# pcb9_21.net
KiCad netlist of a schematic drawn in EAGLE
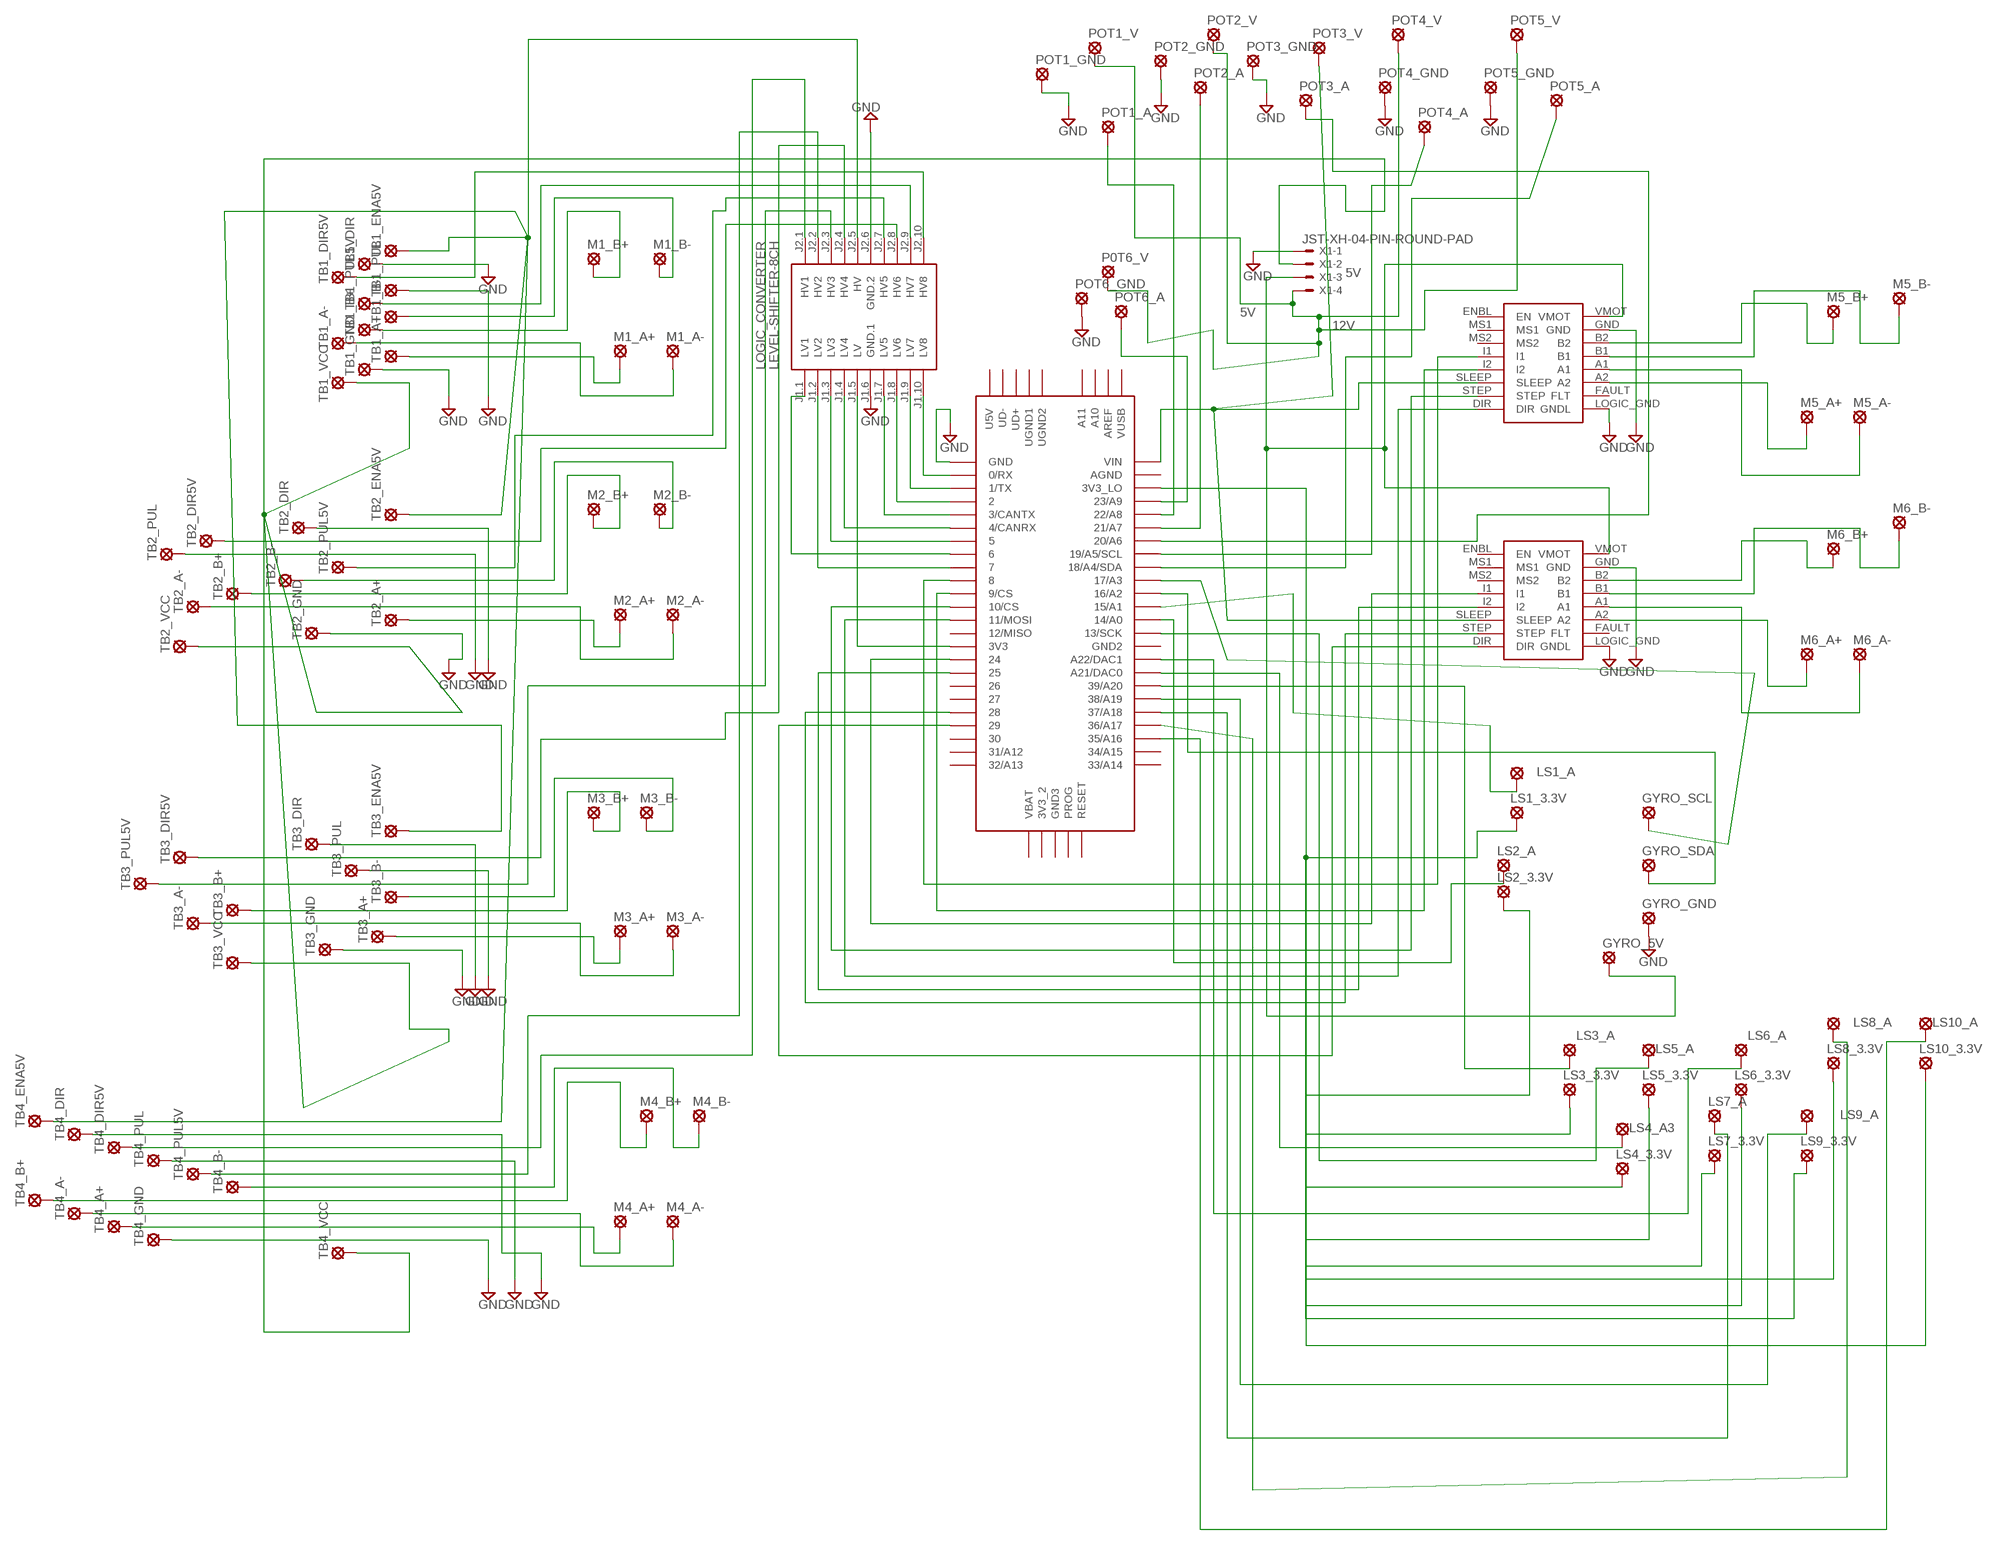
[diagram p0: schematic, sheet 1]

(export (version "E")
  (design (tool "Eeschema 10.0.6"))
  (components
    (comp (ref "GYRO_5V")
      (value "LSP11")
      (footprint "eagle-import:LSP11")
      (libsource (lib "eagle-import") (part "LSP11"))
    )
    (comp (ref "GYRO_GND")
      (value "LSP11")
      (footprint "eagle-import:LSP11")
      (libsource (lib "eagle-import") (part "LSP11"))
    )
    (comp (ref "GYRO_SCL")
      (value "LSP11")
      (footprint "eagle-import:LSP11")
      (libsource (lib "eagle-import") (part "LSP11"))
    )
    (comp (ref "GYRO_SDA")
      (value "LSP11")
      (footprint "eagle-import:LSP11")
      (libsource (lib "eagle-import") (part "LSP11"))
    )
    (comp (ref "LOGIC_CONVERTER")
      (value "LEVEL-SHIFTER-8CH")
      (footprint "eagle-import:LEVEL-SHIFTER-8CH")
      (libsource (lib "eagle-import") (part "LEVEL-SHIFTER-8CH"))
    )
    (comp (ref "LS1_3.3V")
      (value "LSP11")
      (footprint "eagle-import:LSP11")
      (libsource (lib "eagle-import") (part "LSP11"))
    )
    (comp (ref "LS1_A")
      (value "LSP11")
      (footprint "eagle-import:LSP11")
      (libsource (lib "eagle-import") (part "LSP11"))
    )
    (comp (ref "LS2_3.3V")
      (value "LSP11")
      (footprint "eagle-import:LSP11")
      (libsource (lib "eagle-import") (part "LSP11"))
    )
    (comp (ref "LS2_A")
      (value "LSP11")
      (footprint "eagle-import:LSP11")
      (libsource (lib "eagle-import") (part "LSP11"))
    )
    (comp (ref "LS3_3.3V")
      (value "LSP11")
      (footprint "eagle-import:LSP11")
      (libsource (lib "eagle-import") (part "LSP11"))
    )
    (comp (ref "LS3_A")
      (value "LSP11")
      (footprint "eagle-import:LSP11")
      (libsource (lib "eagle-import") (part "LSP11"))
    )
    (comp (ref "LS4_3.3V")
      (value "LSP11")
      (footprint "eagle-import:LSP11")
      (libsource (lib "eagle-import") (part "LSP11"))
    )
    (comp (ref "LS4_A3")
      (value "LSP11")
      (footprint "eagle-import:LSP11")
      (libsource (lib "eagle-import") (part "LSP11"))
    )
    (comp (ref "LS5_3.3V")
      (value "LSP11")
      (footprint "eagle-import:LSP11")
      (libsource (lib "eagle-import") (part "LSP11"))
    )
    (comp (ref "LS5_A")
      (value "LSP11")
      (footprint "eagle-import:LSP11")
      (libsource (lib "eagle-import") (part "LSP11"))
    )
    (comp (ref "LS6_3.3V")
      (value "LSP11")
      (footprint "eagle-import:LSP11")
      (libsource (lib "eagle-import") (part "LSP11"))
    )
    (comp (ref "LS6_A")
      (value "LSP11")
      (footprint "eagle-import:LSP11")
      (libsource (lib "eagle-import") (part "LSP11"))
    )
    (comp (ref "LS7_3.3V")
      (value "LSP11")
      (footprint "eagle-import:LSP11")
      (libsource (lib "eagle-import") (part "LSP11"))
    )
    (comp (ref "LS7_A")
      (value "LSP11")
      (footprint "eagle-import:LSP11")
      (libsource (lib "eagle-import") (part "LSP11"))
    )
    (comp (ref "LS8_3.3V")
      (value "LSP11")
      (footprint "eagle-import:LSP11")
      (libsource (lib "eagle-import") (part "LSP11"))
    )
    (comp (ref "LS8_A")
      (value "LSP11")
      (footprint "eagle-import:LSP11")
      (libsource (lib "eagle-import") (part "LSP11"))
    )
    (comp (ref "LS9_3.3V")
      (value "LSP11")
      (footprint "eagle-import:LSP11")
      (libsource (lib "eagle-import") (part "LSP11"))
    )
    (comp (ref "LS9_A")
      (value "LSP11")
      (footprint "eagle-import:LSP11")
      (libsource (lib "eagle-import") (part "LSP11"))
    )
    (comp (ref "LS10_3.3V")
      (value "LSP11")
      (footprint "eagle-import:LSP11")
      (libsource (lib "eagle-import") (part "LSP11"))
    )
    (comp (ref "LS10_A")
      (value "LSP11")
      (footprint "eagle-import:LSP11")
      (libsource (lib "eagle-import") (part "LSP11"))
    )
    (comp (ref "M1_A+")
      (value "LSP11")
      (footprint "eagle-import:LSP11")
      (libsource (lib "eagle-import") (part "LSP11"))
    )
    (comp (ref "M1_A-")
      (value "LSP11")
      (footprint "eagle-import:LSP11")
      (libsource (lib "eagle-import") (part "LSP11"))
    )
    (comp (ref "M1_B+")
      (value "LSP11")
      (footprint "eagle-import:LSP11")
      (libsource (lib "eagle-import") (part "LSP11"))
    )
    (comp (ref "M1_B-")
      (value "LSP11")
      (footprint "eagle-import:LSP11")
      (libsource (lib "eagle-import") (part "LSP11"))
    )
    (comp (ref "M2_A+")
      (value "LSP11")
      (footprint "eagle-import:LSP11")
      (libsource (lib "eagle-import") (part "LSP11"))
    )
    (comp (ref "M2_A-")
      (value "LSP11")
      (footprint "eagle-import:LSP11")
      (libsource (lib "eagle-import") (part "LSP11"))
    )
    (comp (ref "M2_B+")
      (value "LSP11")
      (footprint "eagle-import:LSP11")
      (libsource (lib "eagle-import") (part "LSP11"))
    )
    (comp (ref "M2_B-")
      (value "LSP11")
      (footprint "eagle-import:LSP11")
      (libsource (lib "eagle-import") (part "LSP11"))
    )
    (comp (ref "M3_A+")
      (value "LSP11")
      (footprint "eagle-import:LSP11")
      (libsource (lib "eagle-import") (part "LSP11"))
    )
    (comp (ref "M3_A-")
      (value "LSP11")
      (footprint "eagle-import:LSP11")
      (libsource (lib "eagle-import") (part "LSP11"))
    )
    (comp (ref "M3_B+")
      (value "LSP11")
      (footprint "eagle-import:LSP11")
      (libsource (lib "eagle-import") (part "LSP11"))
    )
    (comp (ref "M3_B-")
      (value "LSP11")
      (footprint "eagle-import:LSP11")
      (libsource (lib "eagle-import") (part "LSP11"))
    )
    (comp (ref "M4_A+")
      (value "LSP11")
      (footprint "eagle-import:LSP11")
      (libsource (lib "eagle-import") (part "LSP11"))
    )
    (comp (ref "M4_A-")
      (value "LSP11")
      (footprint "eagle-import:LSP11")
      (libsource (lib "eagle-import") (part "LSP11"))
    )
    (comp (ref "M4_B+")
      (value "LSP11")
      (footprint "eagle-import:LSP11")
      (libsource (lib "eagle-import") (part "LSP11"))
    )
    (comp (ref "M4_B-")
      (value "LSP11")
      (footprint "eagle-import:LSP11")
      (libsource (lib "eagle-import") (part "LSP11"))
    )
    (comp (ref "M5_A+")
      (value "LSP11")
      (footprint "eagle-import:LSP11")
      (libsource (lib "eagle-import") (part "LSP11"))
    )
    (comp (ref "M5_A-")
      (value "LSP11")
      (footprint "eagle-import:LSP11")
      (libsource (lib "eagle-import") (part "LSP11"))
    )
    (comp (ref "M5_B+")
      (value "LSP11")
      (footprint "eagle-import:LSP11")
      (libsource (lib "eagle-import") (part "LSP11"))
    )
    (comp (ref "M5_B-")
      (value "LSP11")
      (footprint "eagle-import:LSP11")
      (libsource (lib "eagle-import") (part "LSP11"))
    )
    (comp (ref "M6_A+")
      (value "LSP11")
      (footprint "eagle-import:LSP11")
      (libsource (lib "eagle-import") (part "LSP11"))
    )
    (comp (ref "M6_A-")
      (value "LSP11")
      (footprint "eagle-import:LSP11")
      (libsource (lib "eagle-import") (part "LSP11"))
    )
    (comp (ref "M6_B+")
      (value "LSP11")
      (footprint "eagle-import:LSP11")
      (libsource (lib "eagle-import") (part "LSP11"))
    )
    (comp (ref "M6_B-")
      (value "LSP11")
      (footprint "eagle-import:LSP11")
      (libsource (lib "eagle-import") (part "LSP11"))
    )
    (comp (ref "MP6500_1")
      (value "MP6500THROUGH_HOLE")
      (footprint "eagle-import:MP6500")
      (libsource (lib "eagle-import") (part "MP6500THROUGH_HOLE"))
    )
    (comp (ref "MP6500_2")
      (value "MP6500THROUGH_HOLE")
      (footprint "eagle-import:MP6500")
      (libsource (lib "eagle-import") (part "MP6500THROUGH_HOLE"))
    )
    (comp (ref "P0T6_V")
      (value "LSP11")
      (footprint "eagle-import:LSP11")
      (libsource (lib "eagle-import") (part "LSP11"))
    )
    (comp (ref "POT1_A")
      (value "LSP11")
      (footprint "eagle-import:LSP11")
      (libsource (lib "eagle-import") (part "LSP11"))
    )
    (comp (ref "POT1_GND")
      (value "LSP11")
      (footprint "eagle-import:LSP11")
      (libsource (lib "eagle-import") (part "LSP11"))
    )
    (comp (ref "POT1_V")
      (value "LSP11")
      (footprint "eagle-import:LSP11")
      (libsource (lib "eagle-import") (part "LSP11"))
    )
    (comp (ref "POT2_A")
      (value "LSP11")
      (footprint "eagle-import:LSP11")
      (libsource (lib "eagle-import") (part "LSP11"))
    )
    (comp (ref "POT2_GND")
      (value "LSP11")
      (footprint "eagle-import:LSP11")
      (libsource (lib "eagle-import") (part "LSP11"))
    )
    (comp (ref "POT2_V")
      (value "LSP11")
      (footprint "eagle-import:LSP11")
      (libsource (lib "eagle-import") (part "LSP11"))
    )
    (comp (ref "POT3_A")
      (value "LSP11")
      (footprint "eagle-import:LSP11")
      (libsource (lib "eagle-import") (part "LSP11"))
    )
    (comp (ref "POT3_GND")
      (value "LSP11")
      (footprint "eagle-import:LSP11")
      (libsource (lib "eagle-import") (part "LSP11"))
    )
    (comp (ref "POT3_V")
      (value "LSP11")
      (footprint "eagle-import:LSP11")
      (libsource (lib "eagle-import") (part "LSP11"))
    )
    (comp (ref "POT4_A")
      (value "LSP11")
      (footprint "eagle-import:LSP11")
      (libsource (lib "eagle-import") (part "LSP11"))
    )
    (comp (ref "POT4_GND")
      (value "LSP11")
      (footprint "eagle-import:LSP11")
      (libsource (lib "eagle-import") (part "LSP11"))
    )
    (comp (ref "POT4_V")
      (value "LSP11")
      (footprint "eagle-import:LSP11")
      (libsource (lib "eagle-import") (part "LSP11"))
    )
    (comp (ref "POT5_A")
      (value "LSP11")
      (footprint "eagle-import:LSP11")
      (libsource (lib "eagle-import") (part "LSP11"))
    )
    (comp (ref "POT5_GND")
      (value "LSP11")
      (footprint "eagle-import:LSP11")
      (libsource (lib "eagle-import") (part "LSP11"))
    )
    (comp (ref "POT5_V")
      (value "LSP11")
      (footprint "eagle-import:LSP11")
      (libsource (lib "eagle-import") (part "LSP11"))
    )
    (comp (ref "POT6_A")
      (value "LSP11")
      (footprint "eagle-import:LSP11")
      (libsource (lib "eagle-import") (part "LSP11"))
    )
    (comp (ref "POT6_GND")
      (value "LSP11")
      (footprint "eagle-import:LSP11")
      (libsource (lib "eagle-import") (part "LSP11"))
    )
    (comp (ref "TB1_A+")
      (value "LSP11")
      (footprint "eagle-import:LSP11")
      (libsource (lib "eagle-import") (part "LSP11"))
    )
    (comp (ref "TB1_A-")
      (value "LSP11")
      (footprint "eagle-import:LSP11")
      (libsource (lib "eagle-import") (part "LSP11"))
    )
    (comp (ref "TB1_B+")
      (value "LSP11")
      (footprint "eagle-import:LSP11")
      (libsource (lib "eagle-import") (part "LSP11"))
    )
    (comp (ref "TB1_B-")
      (value "LSP11")
      (footprint "eagle-import:LSP11")
      (libsource (lib "eagle-import") (part "LSP11"))
    )
    (comp (ref "TB1_DIR")
      (value "LSP11")
      (footprint "eagle-import:LSP11")
      (libsource (lib "eagle-import") (part "LSP11"))
    )
    (comp (ref "TB1_DIR5V")
      (value "LSP11")
      (footprint "eagle-import:LSP11")
      (libsource (lib "eagle-import") (part "LSP11"))
    )
    (comp (ref "TB1_ENA5V")
      (value "LSP11")
      (footprint "eagle-import:LSP11")
      (libsource (lib "eagle-import") (part "LSP11"))
    )
    (comp (ref "TB1_GND")
      (value "LSP11")
      (footprint "eagle-import:LSP11")
      (libsource (lib "eagle-import") (part "LSP11"))
    )
    (comp (ref "TB1_PUL")
      (value "LSP11")
      (footprint "eagle-import:LSP11")
      (libsource (lib "eagle-import") (part "LSP11"))
    )
    (comp (ref "TB1_PUL5V")
      (value "LSP11")
      (footprint "eagle-import:LSP11")
      (libsource (lib "eagle-import") (part "LSP11"))
    )
    (comp (ref "TB1_VCC")
      (value "LSP11")
      (footprint "eagle-import:LSP11")
      (libsource (lib "eagle-import") (part "LSP11"))
    )
    (comp (ref "TB2_A+")
      (value "LSP11")
      (footprint "eagle-import:LSP11")
      (libsource (lib "eagle-import") (part "LSP11"))
    )
    (comp (ref "TB2_A-")
      (value "LSP11")
      (footprint "eagle-import:LSP11")
      (libsource (lib "eagle-import") (part "LSP11"))
    )
    (comp (ref "TB2_B+")
      (value "LSP11")
      (footprint "eagle-import:LSP11")
      (libsource (lib "eagle-import") (part "LSP11"))
    )
    (comp (ref "TB2_B-")
      (value "LSP11")
      (footprint "eagle-import:LSP11")
      (libsource (lib "eagle-import") (part "LSP11"))
    )
    (comp (ref "TB2_DIR")
      (value "LSP11")
      (footprint "eagle-import:LSP11")
      (libsource (lib "eagle-import") (part "LSP11"))
    )
    (comp (ref "TB2_DIR5V")
      (value "LSP11")
      (footprint "eagle-import:LSP11")
      (libsource (lib "eagle-import") (part "LSP11"))
    )
    (comp (ref "TB2_ENA5V")
      (value "LSP11")
      (footprint "eagle-import:LSP11")
      (libsource (lib "eagle-import") (part "LSP11"))
    )
    (comp (ref "TB2_GND")
      (value "LSP11")
      (footprint "eagle-import:LSP11")
      (libsource (lib "eagle-import") (part "LSP11"))
    )
    (comp (ref "TB2_PUL")
      (value "LSP11")
      (footprint "eagle-import:LSP11")
      (libsource (lib "eagle-import") (part "LSP11"))
    )
    (comp (ref "TB2_PUL5V")
      (value "LSP11")
      (footprint "eagle-import:LSP11")
      (libsource (lib "eagle-import") (part "LSP11"))
    )
    (comp (ref "TB2_VCC")
      (value "LSP11")
      (footprint "eagle-import:LSP11")
      (libsource (lib "eagle-import") (part "LSP11"))
    )
    (comp (ref "TB3_A+")
      (value "LSP11")
      (footprint "eagle-import:LSP11")
      (libsource (lib "eagle-import") (part "LSP11"))
    )
    (comp (ref "TB3_A-")
      (value "LSP11")
      (footprint "eagle-import:LSP11")
      (libsource (lib "eagle-import") (part "LSP11"))
    )
    (comp (ref "TB3_B+")
      (value "LSP11")
      (footprint "eagle-import:LSP11")
      (libsource (lib "eagle-import") (part "LSP11"))
    )
    (comp (ref "TB3_B-")
      (value "LSP11")
      (footprint "eagle-import:LSP11")
      (libsource (lib "eagle-import") (part "LSP11"))
    )
    (comp (ref "TB3_DIR")
      (value "LSP11")
      (footprint "eagle-import:LSP11")
      (libsource (lib "eagle-import") (part "LSP11"))
    )
    (comp (ref "TB3_DIR5V")
      (value "LSP11")
      (footprint "eagle-import:LSP11")
      (libsource (lib "eagle-import") (part "LSP11"))
    )
    (comp (ref "TB3_ENA5V")
      (value "LSP11")
      (footprint "eagle-import:LSP11")
      (libsource (lib "eagle-import") (part "LSP11"))
    )
    (comp (ref "TB3_GND")
      (value "LSP11")
      (footprint "eagle-import:LSP11")
      (libsource (lib "eagle-import") (part "LSP11"))
    )
    (comp (ref "TB3_PUL")
      (value "LSP11")
      (footprint "eagle-import:LSP11")
      (libsource (lib "eagle-import") (part "LSP11"))
    )
    (comp (ref "TB3_PUL5V")
      (value "LSP11")
      (footprint "eagle-import:LSP11")
      (libsource (lib "eagle-import") (part "LSP11"))
    )
    (comp (ref "TB3_VCC")
      (value "LSP11")
      (footprint "eagle-import:LSP11")
      (libsource (lib "eagle-import") (part "LSP11"))
    )
    (comp (ref "TB4_A+")
      (value "LSP11")
      (footprint "eagle-import:LSP11")
      (libsource (lib "eagle-import") (part "LSP11"))
    )
    (comp (ref "TB4_A-")
      (value "LSP11")
      (footprint "eagle-import:LSP11")
      (libsource (lib "eagle-import") (part "LSP11"))
    )
    (comp (ref "TB4_B+")
      (value "LSP11")
      (footprint "eagle-import:LSP11")
      (libsource (lib "eagle-import") (part "LSP11"))
    )
    (comp (ref "TB4_B-")
      (value "LSP11")
      (footprint "eagle-import:LSP11")
      (libsource (lib "eagle-import") (part "LSP11"))
    )
    (comp (ref "TB4_DIR")
      (value "LSP11")
      (footprint "eagle-import:LSP11")
      (libsource (lib "eagle-import") (part "LSP11"))
    )
    (comp (ref "TB4_DIR5V")
      (value "LSP11")
      (footprint "eagle-import:LSP11")
      (libsource (lib "eagle-import") (part "LSP11"))
    )
    (comp (ref "TB4_ENA5V")
      (value "LSP11")
      (footprint "eagle-import:LSP11")
      (libsource (lib "eagle-import") (part "LSP11"))
    )
    (comp (ref "TB4_GND")
      (value "LSP11")
      (footprint "eagle-import:LSP11")
      (libsource (lib "eagle-import") (part "LSP11"))
    )
    (comp (ref "TB4_PUL")
      (value "LSP11")
      (footprint "eagle-import:LSP11")
      (libsource (lib "eagle-import") (part "LSP11"))
    )
    (comp (ref "TB4_PUL5V")
      (value "LSP11")
      (footprint "eagle-import:LSP11")
      (libsource (lib "eagle-import") (part "LSP11"))
    )
    (comp (ref "TB4_VCC")
      (value "LSP11")
      (footprint "eagle-import:LSP11")
      (libsource (lib "eagle-import") (part "LSP11"))
    )
    (comp (ref "TEENSY4.1")
      (value "TEENSY_3.5/3.6")
      (footprint "eagle-import:TEENSY_3.5_3.6")
      (libsource (lib "eagle-import") (part "TEENSY_3.5/3.6"))
    )
    (comp (ref "X1")
      (value "JST-XH-04-PIN-ROUND-PAD")
      (footprint "eagle-import:JST-XH-04-PACKAGE-ROUND-PAD")
      (libsource (lib "eagle-import") (part "JST-XH-04-PIN-ROUND-PAD"))
    )
  )
  (nets
    (net (code "1") (name "/5V") (class "Default")
      (node (ref "GYRO_5V") (pin "MP") (pinfunction "MP_MP") (pintype "passive"))
      (node (ref "MP6500_1") (pin "VMOT") (pinfunction "VMOT_VMOT") (pintype "bidirectional"))
      (node (ref "MP6500_2") (pin "VMOT") (pinfunction "VMOT_VMOT") (pintype "bidirectional"))
      (node (ref "TB1_VCC") (pin "MP") (pinfunction "MP_MP") (pintype "passive"))
      (node (ref "TB2_VCC") (pin "MP") (pinfunction "MP_MP") (pintype "passive"))
      (node (ref "TB3_VCC") (pin "MP") (pinfunction "MP_MP") (pintype "passive"))
      (node (ref "TB4_VCC") (pin "MP") (pinfunction "MP_MP") (pintype "passive"))
      (node (ref "X1") (pin "2") (pinfunction "S_2") (pintype "passive"))
      (node (ref "X1") (pin "3") (pinfunction "S_3") (pintype "passive"))
    )
    (net (code "2") (name "/12V") (class "Default")
      (node (ref "P0T6_V") (pin "MP") (pinfunction "MP_MP") (pintype "passive"))
      (node (ref "POT1_V") (pin "MP") (pinfunction "MP_MP") (pintype "passive"))
      (node (ref "POT2_V") (pin "MP") (pinfunction "MP_MP") (pintype "passive"))
      (node (ref "POT4_V") (pin "MP") (pinfunction "MP_MP") (pintype "passive"))
      (node (ref "POT5_V") (pin "MP") (pinfunction "MP_MP") (pintype "passive"))
      (node (ref "X1") (pin "4") (pinfunction "S_4") (pintype "passive"))
    )
    (net (code "3") (name "GND") (class "Default")
      (node (ref "GYRO_GND") (pin "MP") (pinfunction "MP_MP") (pintype "passive"))
      (node (ref "LOGIC_CONVERTER") (pin "J1.6") (pinfunction "GND.1_J1.6") (pintype "power_in"))
      (node (ref "LOGIC_CONVERTER") (pin "J2.6") (pinfunction "GND.2_J2.6") (pintype "power_in"))
      (node (ref "MP6500_1") (pin "GND") (pinfunction "GND_GND") (pintype "bidirectional"))
      (node (ref "MP6500_1") (pin "LOGIC_GND") (pinfunction "GNDL_LOGIC_GND") (pintype "bidirectional"))
      (node (ref "MP6500_2") (pin "GND") (pinfunction "GND_GND") (pintype "bidirectional"))
      (node (ref "MP6500_2") (pin "LOGIC_GND") (pinfunction "GNDL_LOGIC_GND") (pintype "bidirectional"))
      (node (ref "POT1_GND") (pin "MP") (pinfunction "MP_MP") (pintype "passive"))
      (node (ref "POT2_GND") (pin "MP") (pinfunction "MP_MP") (pintype "passive"))
      (node (ref "POT3_GND") (pin "MP") (pinfunction "MP_MP") (pintype "passive"))
      (node (ref "POT4_GND") (pin "MP") (pinfunction "MP_MP") (pintype "passive"))
      (node (ref "POT5_GND") (pin "MP") (pinfunction "MP_MP") (pintype "passive"))
      (node (ref "POT6_GND") (pin "MP") (pinfunction "MP_MP") (pintype "passive"))
      (node (ref "TB1_DIR") (pin "MP") (pinfunction "MP_MP") (pintype "passive"))
      (node (ref "TB1_GND") (pin "MP") (pinfunction "MP_MP") (pintype "passive"))
      (node (ref "TB1_PUL") (pin "MP") (pinfunction "MP_MP") (pintype "passive"))
      (node (ref "TB2_DIR") (pin "MP") (pinfunction "MP_MP") (pintype "passive"))
      (node (ref "TB2_GND") (pin "MP") (pinfunction "MP_MP") (pintype "passive"))
      (node (ref "TB2_PUL") (pin "MP") (pinfunction "MP_MP") (pintype "passive"))
      (node (ref "TB3_DIR") (pin "MP") (pinfunction "MP_MP") (pintype "passive"))
      (node (ref "TB3_GND") (pin "MP") (pinfunction "MP_MP") (pintype "passive"))
      (node (ref "TB3_PUL") (pin "MP") (pinfunction "MP_MP") (pintype "passive"))
      (node (ref "TB4_DIR") (pin "MP") (pinfunction "MP_MP") (pintype "passive"))
      (node (ref "TB4_GND") (pin "MP") (pinfunction "MP_MP") (pintype "passive"))
      (node (ref "TB4_PUL") (pin "MP") (pinfunction "MP_MP") (pintype "passive"))
      (node (ref "TEENSY4.1") (pin "GND") (pinfunction "GND_GND") (pintype "bidirectional"))
      (node (ref "X1") (pin "1") (pinfunction "S_1") (pintype "passive"))
    )
    (net (code "4") (name "Net-(GYRO_SCL-PadMP)") (class "Default")
      (node (ref "GYRO_SCL") (pin "MP") (pinfunction "MP_MP") (pintype "passive"))
      (node (ref "TEENSY4.1") (pin "17/A3") (pinfunction "17/A3_17/A3") (pintype "bidirectional"))
    )
    (net (code "5") (name "Net-(GYRO_SDA-PadMP)") (class "Default")
      (node (ref "GYRO_SDA") (pin "MP") (pinfunction "MP_MP") (pintype "passive"))
      (node (ref "TEENSY4.1") (pin "16/A2") (pinfunction "16/A2_16/A2") (pintype "bidirectional"))
    )
    (net (code "6") (name "Net-(LOGIC_CONVERTER-HV)") (class "Default")
      (node (ref "LOGIC_CONVERTER") (pin "J2.5") (pinfunction "HV_J2.5") (pintype "power_in"))
      (node (ref "TB1_ENA5V") (pin "MP") (pinfunction "MP_MP") (pintype "passive"))
      (node (ref "TB2_ENA5V") (pin "MP") (pinfunction "MP_MP") (pintype "passive"))
      (node (ref "TB3_ENA5V") (pin "MP") (pinfunction "MP_MP") (pintype "passive"))
      (node (ref "TB4_ENA5V") (pin "MP") (pinfunction "MP_MP") (pintype "passive"))
    )
    (net (code "7") (name "Net-(LOGIC_CONVERTER-HV1)") (class "Default")
      (node (ref "LOGIC_CONVERTER") (pin "J2.1") (pinfunction "HV1_J2.1") (pintype "bidirectional"))
      (node (ref "TB4_DIR5V") (pin "MP") (pinfunction "MP_MP") (pintype "passive"))
    )
    (net (code "8") (name "Net-(LOGIC_CONVERTER-HV2)") (class "Default")
      (node (ref "LOGIC_CONVERTER") (pin "J2.2") (pinfunction "HV2_J2.2") (pintype "bidirectional"))
      (node (ref "TB4_PUL5V") (pin "MP") (pinfunction "MP_MP") (pintype "passive"))
    )
    (net (code "9") (name "Net-(LOGIC_CONVERTER-HV3)") (class "Default")
      (node (ref "LOGIC_CONVERTER") (pin "J2.3") (pinfunction "HV3_J2.3") (pintype "bidirectional"))
      (node (ref "TB3_PUL5V") (pin "MP") (pinfunction "MP_MP") (pintype "passive"))
    )
    (net (code "10") (name "Net-(LOGIC_CONVERTER-HV4)") (class "Default")
      (node (ref "LOGIC_CONVERTER") (pin "J2.4") (pinfunction "HV4_J2.4") (pintype "bidirectional"))
      (node (ref "TB3_DIR5V") (pin "MP") (pinfunction "MP_MP") (pintype "passive"))
    )
    (net (code "11") (name "Net-(LOGIC_CONVERTER-HV5)") (class "Default")
      (node (ref "LOGIC_CONVERTER") (pin "J2.7") (pinfunction "HV5_J2.7") (pintype "bidirectional"))
      (node (ref "TB2_PUL5V") (pin "MP") (pinfunction "MP_MP") (pintype "passive"))
    )
    (net (code "12") (name "Net-(LOGIC_CONVERTER-HV6)") (class "Default")
      (node (ref "LOGIC_CONVERTER") (pin "J2.8") (pinfunction "HV6_J2.8") (pintype "bidirectional"))
      (node (ref "TB2_DIR5V") (pin "MP") (pinfunction "MP_MP") (pintype "passive"))
    )
    (net (code "13") (name "Net-(LOGIC_CONVERTER-HV7)") (class "Default")
      (node (ref "LOGIC_CONVERTER") (pin "J2.9") (pinfunction "HV7_J2.9") (pintype "bidirectional"))
      (node (ref "TB1_PUL5V") (pin "MP") (pinfunction "MP_MP") (pintype "passive"))
    )
    (net (code "14") (name "Net-(LOGIC_CONVERTER-HV8)") (class "Default")
      (node (ref "LOGIC_CONVERTER") (pin "J2.10") (pinfunction "HV8_J2.10") (pintype "bidirectional"))
      (node (ref "TB1_DIR5V") (pin "MP") (pinfunction "MP_MP") (pintype "passive"))
    )
    (net (code "15") (name "Net-(LOGIC_CONVERTER-LV)") (class "Default")
      (node (ref "LOGIC_CONVERTER") (pin "J1.5") (pinfunction "LV_J1.5") (pintype "power_in"))
      (node (ref "TEENSY4.1") (pin "3V3") (pinfunction "3V3_3V3") (pintype "bidirectional"))
    )
    (net (code "16") (name "Net-(LOGIC_CONVERTER-LV1)") (class "Default")
      (node (ref "LOGIC_CONVERTER") (pin "J1.1") (pinfunction "LV1_J1.1") (pintype "bidirectional"))
      (node (ref "TEENSY4.1") (pin "6") (pinfunction "6_6") (pintype "bidirectional"))
    )
    (net (code "17") (name "Net-(LOGIC_CONVERTER-LV2)") (class "Default")
      (node (ref "LOGIC_CONVERTER") (pin "J1.2") (pinfunction "LV2_J1.2") (pintype "bidirectional"))
      (node (ref "TEENSY4.1") (pin "7") (pinfunction "7_7") (pintype "bidirectional"))
    )
    (net (code "18") (name "Net-(LOGIC_CONVERTER-LV3)") (class "Default")
      (node (ref "LOGIC_CONVERTER") (pin "J1.3") (pinfunction "LV3_J1.3") (pintype "bidirectional"))
      (node (ref "TEENSY4.1") (pin "5") (pinfunction "5_5") (pintype "bidirectional"))
    )
    (net (code "19") (name "Net-(LOGIC_CONVERTER-LV4)") (class "Default")
      (node (ref "LOGIC_CONVERTER") (pin "J1.4") (pinfunction "LV4_J1.4") (pintype "bidirectional"))
      (node (ref "TEENSY4.1") (pin "4/CANRX") (pinfunction "4/CANRX_4/CANRX") (pintype "bidirectional"))
    )
    (net (code "20") (name "Net-(LOGIC_CONVERTER-LV5)") (class "Default")
      (node (ref "LOGIC_CONVERTER") (pin "J1.7") (pinfunction "LV5_J1.7") (pintype "bidirectional"))
      (node (ref "TEENSY4.1") (pin "3/CANTX") (pinfunction "3/CANTX_3/CANTX") (pintype "bidirectional"))
    )
    (net (code "21") (name "Net-(LOGIC_CONVERTER-LV6)") (class "Default")
      (node (ref "LOGIC_CONVERTER") (pin "J1.8") (pinfunction "LV6_J1.8") (pintype "bidirectional"))
      (node (ref "TEENSY4.1") (pin "2") (pinfunction "2_2") (pintype "bidirectional"))
    )
    (net (code "22") (name "Net-(LOGIC_CONVERTER-LV7)") (class "Default")
      (node (ref "LOGIC_CONVERTER") (pin "J1.9") (pinfunction "LV7_J1.9") (pintype "bidirectional"))
      (node (ref "TEENSY4.1") (pin "1/TX") (pinfunction "1/TX_1/TX") (pintype "bidirectional"))
    )
    (net (code "23") (name "Net-(LOGIC_CONVERTER-LV8)") (class "Default")
      (node (ref "LOGIC_CONVERTER") (pin "J1.10") (pinfunction "LV8_J1.10") (pintype "bidirectional"))
      (node (ref "TEENSY4.1") (pin "0/RX") (pinfunction "0/RX_0/RX") (pintype "bidirectional"))
    )
    (net (code "24") (name "Net-(LS1_A-PadMP)") (class "Default")
      (node (ref "LS1_A") (pin "MP") (pinfunction "MP_MP") (pintype "passive"))
      (node (ref "TEENSY4.1") (pin "15/A1") (pinfunction "15/A1_15/A1") (pintype "bidirectional"))
    )
    (net (code "25") (name "Net-(LS2_A-PadMP)") (class "Default")
      (node (ref "LS2_A") (pin "MP") (pinfunction "MP_MP") (pintype "passive"))
      (node (ref "TEENSY4.1") (pin "14/A0") (pinfunction "14/A0_14/A0") (pintype "bidirectional"))
    )
    (net (code "26") (name "Net-(LS3_A-PadMP)") (class "Default")
      (node (ref "LS3_A") (pin "MP") (pinfunction "MP_MP") (pintype "passive"))
      (node (ref "TEENSY4.1") (pin "39/A20") (pinfunction "39/A20_39/A20") (pintype "bidirectional"))
    )
    (net (code "27") (name "Net-(LS5_A-PadMP)") (class "Default")
      (node (ref "LS5_A") (pin "MP") (pinfunction "MP_MP") (pintype "passive"))
      (node (ref "TEENSY4.1") (pin "13/SCK") (pinfunction "13/SCK_13/SCK") (pintype "bidirectional"))
    )
    (net (code "28") (name "Net-(LS6_A-PadMP)") (class "Default")
      (node (ref "LS6_A") (pin "MP") (pinfunction "MP_MP") (pintype "passive"))
      (node (ref "TEENSY4.1") (pin "A22/DAC1") (pinfunction "A22/DAC1_A22/DAC1") (pintype "bidirectional"))
    )
    (net (code "29") (name "Net-(LS7_A-PadMP)") (class "Default")
      (node (ref "LS7_A") (pin "MP") (pinfunction "MP_MP") (pintype "passive"))
      (node (ref "TEENSY4.1") (pin "37/A18") (pinfunction "37/A18_37/A18") (pintype "bidirectional"))
    )
    (net (code "30") (name "Net-(LS8_A-PadMP)") (class "Default")
      (node (ref "LS8_A") (pin "MP") (pinfunction "MP_MP") (pintype "passive"))
      (node (ref "TEENSY4.1") (pin "36/A17") (pinfunction "36/A17_36/A17") (pintype "bidirectional"))
    )
    (net (code "31") (name "Net-(LS9_A-PadMP)") (class "Default")
      (node (ref "LS9_A") (pin "MP") (pinfunction "MP_MP") (pintype "passive"))
      (node (ref "TEENSY4.1") (pin "38/A19") (pinfunction "38/A19_38/A19") (pintype "bidirectional"))
    )
    (net (code "32") (name "Net-(LS10_3.3V-PadMP)") (class "Default")
      (node (ref "LS10_3.3V") (pin "MP") (pinfunction "MP_MP") (pintype "passive"))
      (node (ref "LS1_3.3V") (pin "MP") (pinfunction "MP_MP") (pintype "passive"))
      (node (ref "LS2_3.3V") (pin "MP") (pinfunction "MP_MP") (pintype "passive"))
      (node (ref "LS3_3.3V") (pin "MP") (pinfunction "MP_MP") (pintype "passive"))
      (node (ref "LS4_3.3V") (pin "MP") (pinfunction "MP_MP") (pintype "passive"))
      (node (ref "LS5_3.3V") (pin "MP") (pinfunction "MP_MP") (pintype "passive"))
      (node (ref "LS6_3.3V") (pin "MP") (pinfunction "MP_MP") (pintype "passive"))
      (node (ref "LS7_3.3V") (pin "MP") (pinfunction "MP_MP") (pintype "passive"))
      (node (ref "LS8_3.3V") (pin "MP") (pinfunction "MP_MP") (pintype "passive"))
      (node (ref "LS9_3.3V") (pin "MP") (pinfunction "MP_MP") (pintype "passive"))
      (node (ref "TEENSY4.1") (pin "3V3_LO") (pinfunction "3V3_LO_3V3_LO") (pintype "bidirectional"))
    )
    (net (code "33") (name "Net-(LS10_A-PadMP)") (class "Default")
      (node (ref "LS10_A") (pin "MP") (pinfunction "MP_MP") (pintype "passive"))
      (node (ref "TEENSY4.1") (pin "35/A16") (pinfunction "35/A16_35/A16") (pintype "bidirectional"))
    )
    (net (code "34") (name "Net-(M1_A+-PadMP)") (class "Default")
      (node (ref "M1_A+") (pin "MP") (pinfunction "MP_MP") (pintype "passive"))
      (node (ref "TB1_A+") (pin "MP") (pinfunction "MP_MP") (pintype "passive"))
    )
    (net (code "35") (name "Net-(M1_A--PadMP)") (class "Default")
      (node (ref "M1_A-") (pin "MP") (pinfunction "MP_MP") (pintype "passive"))
      (node (ref "TB1_A-") (pin "MP") (pinfunction "MP_MP") (pintype "passive"))
    )
    (net (code "36") (name "Net-(M1_B+-PadMP)") (class "Default")
      (node (ref "M1_B+") (pin "MP") (pinfunction "MP_MP") (pintype "passive"))
      (node (ref "TB1_B+") (pin "MP") (pinfunction "MP_MP") (pintype "passive"))
    )
    (net (code "37") (name "Net-(M1_B--PadMP)") (class "Default")
      (node (ref "M1_B-") (pin "MP") (pinfunction "MP_MP") (pintype "passive"))
      (node (ref "TB1_B-") (pin "MP") (pinfunction "MP_MP") (pintype "passive"))
    )
    (net (code "38") (name "Net-(M2_A+-PadMP)") (class "Default")
      (node (ref "M2_A+") (pin "MP") (pinfunction "MP_MP") (pintype "passive"))
      (node (ref "TB2_A+") (pin "MP") (pinfunction "MP_MP") (pintype "passive"))
    )
    (net (code "39") (name "Net-(M2_A--PadMP)") (class "Default")
      (node (ref "M2_A-") (pin "MP") (pinfunction "MP_MP") (pintype "passive"))
      (node (ref "TB2_A-") (pin "MP") (pinfunction "MP_MP") (pintype "passive"))
    )
    (net (code "40") (name "Net-(M2_B+-PadMP)") (class "Default")
      (node (ref "M2_B+") (pin "MP") (pinfunction "MP_MP") (pintype "passive"))
      (node (ref "TB2_B+") (pin "MP") (pinfunction "MP_MP") (pintype "passive"))
    )
    (net (code "41") (name "Net-(M2_B--PadMP)") (class "Default")
      (node (ref "M2_B-") (pin "MP") (pinfunction "MP_MP") (pintype "passive"))
      (node (ref "TB2_B-") (pin "MP") (pinfunction "MP_MP") (pintype "passive"))
    )
    (net (code "42") (name "Net-(M3_A+-PadMP)") (class "Default")
      (node (ref "M3_A+") (pin "MP") (pinfunction "MP_MP") (pintype "passive"))
      (node (ref "TB3_A+") (pin "MP") (pinfunction "MP_MP") (pintype "passive"))
    )
    (net (code "43") (name "Net-(M3_A--PadMP)") (class "Default")
      (node (ref "M3_A-") (pin "MP") (pinfunction "MP_MP") (pintype "passive"))
      (node (ref "TB3_A-") (pin "MP") (pinfunction "MP_MP") (pintype "passive"))
    )
    (net (code "44") (name "Net-(M3_B+-PadMP)") (class "Default")
      (node (ref "M3_B+") (pin "MP") (pinfunction "MP_MP") (pintype "passive"))
      (node (ref "TB3_B+") (pin "MP") (pinfunction "MP_MP") (pintype "passive"))
    )
    (net (code "45") (name "Net-(M3_B--PadMP)") (class "Default")
      (node (ref "M3_B-") (pin "MP") (pinfunction "MP_MP") (pintype "passive"))
      (node (ref "TB3_B-") (pin "MP") (pinfunction "MP_MP") (pintype "passive"))
    )
    (net (code "46") (name "Net-(M4_A+-PadMP)") (class "Default")
      (node (ref "M4_A+") (pin "MP") (pinfunction "MP_MP") (pintype "passive"))
      (node (ref "TB4_A+") (pin "MP") (pinfunction "MP_MP") (pintype "passive"))
    )
    (net (code "47") (name "Net-(M4_A--PadMP)") (class "Default")
      (node (ref "M4_A-") (pin "MP") (pinfunction "MP_MP") (pintype "passive"))
      (node (ref "TB4_A-") (pin "MP") (pinfunction "MP_MP") (pintype "passive"))
    )
    (net (code "48") (name "Net-(M4_B+-PadMP)") (class "Default")
      (node (ref "M4_B+") (pin "MP") (pinfunction "MP_MP") (pintype "passive"))
      (node (ref "TB4_B+") (pin "MP") (pinfunction "MP_MP") (pintype "passive"))
    )
    (net (code "49") (name "Net-(M4_B--PadMP)") (class "Default")
      (node (ref "M4_B-") (pin "MP") (pinfunction "MP_MP") (pintype "passive"))
      (node (ref "TB4_B-") (pin "MP") (pinfunction "MP_MP") (pintype "passive"))
    )
    (net (code "50") (name "Net-(M5_A+-PadMP)") (class "Default")
      (node (ref "M5_A+") (pin "MP") (pinfunction "MP_MP") (pintype "passive"))
      (node (ref "MP6500_1") (pin "A2") (pinfunction "A2_A2") (pintype "bidirectional"))
    )
    (net (code "51") (name "Net-(M5_A--PadMP)") (class "Default")
      (node (ref "M5_A-") (pin "MP") (pinfunction "MP_MP") (pintype "passive"))
      (node (ref "MP6500_1") (pin "A1") (pinfunction "A1_A1") (pintype "bidirectional"))
    )
    (net (code "52") (name "Net-(M5_B+-PadMP)") (class "Default")
      (node (ref "M5_B+") (pin "MP") (pinfunction "MP_MP") (pintype "passive"))
      (node (ref "MP6500_1") (pin "B2") (pinfunction "B2_B2") (pintype "bidirectional"))
    )
    (net (code "53") (name "Net-(M5_B--PadMP)") (class "Default")
      (node (ref "M5_B-") (pin "MP") (pinfunction "MP_MP") (pintype "passive"))
      (node (ref "MP6500_1") (pin "B1") (pinfunction "B1_B1") (pintype "bidirectional"))
    )
    (net (code "54") (name "Net-(M6_A+-PadMP)") (class "Default")
      (node (ref "M6_A+") (pin "MP") (pinfunction "MP_MP") (pintype "passive"))
      (node (ref "MP6500_2") (pin "A2") (pinfunction "A2_A2") (pintype "bidirectional"))
    )
    (net (code "55") (name "Net-(M6_A--PadMP)") (class "Default")
      (node (ref "M6_A-") (pin "MP") (pinfunction "MP_MP") (pintype "passive"))
      (node (ref "MP6500_2") (pin "A1") (pinfunction "A1_A1") (pintype "bidirectional"))
    )
    (net (code "56") (name "Net-(M6_B+-PadMP)") (class "Default")
      (node (ref "M6_B+") (pin "MP") (pinfunction "MP_MP") (pintype "passive"))
      (node (ref "MP6500_2") (pin "B2") (pinfunction "B2_B2") (pintype "bidirectional"))
    )
    (net (code "57") (name "Net-(M6_B--PadMP)") (class "Default")
      (node (ref "M6_B-") (pin "MP") (pinfunction "MP_MP") (pintype "passive"))
      (node (ref "MP6500_2") (pin "B1") (pinfunction "B1_B1") (pintype "bidirectional"))
    )
    (net (code "58") (name "Net-(MP6500_1-PadDIR)") (class "Default")
      (node (ref "MP6500_1") (pin "DIR") (pinfunction "DIR_DIR") (pintype "bidirectional"))
      (node (ref "TEENSY4.1") (pin "11/MOSI") (pinfunction "11/MOSI_11/MOSI") (pintype "bidirectional"))
    )
    (net (code "59") (name "Net-(MP6500_1-PadI1)") (class "Default")
      (node (ref "MP6500_1") (pin "I1") (pinfunction "I1_I1") (pintype "bidirectional"))
      (node (ref "TEENSY4.1") (pin "8") (pinfunction "8_8") (pintype "bidirectional"))
    )
    (net (code "60") (name "Net-(MP6500_1-PadI2)") (class "Default")
      (node (ref "MP6500_1") (pin "I2") (pinfunction "I2_I2") (pintype "bidirectional"))
      (node (ref "TEENSY4.1") (pin "9/CS") (pinfunction "9/CS_9/CS") (pintype "bidirectional"))
    )
    (net (code "61") (name "Net-(MP6500_1-PadSLEEP)") (class "Default")
      (node (ref "MP6500_1") (pin "SLEEP") (pinfunction "SLEEP_SLEEP") (pintype "bidirectional"))
      (node (ref "MP6500_2") (pin "SLEEP") (pinfunction "SLEEP_SLEEP") (pintype "bidirectional"))
      (node (ref "POT3_V") (pin "MP") (pinfunction "MP_MP") (pintype "passive"))
      (node (ref "TEENSY4.1") (pin "VIN") (pinfunction "VIN_VIN") (pintype "bidirectional"))
    )
    (net (code "62") (name "Net-(MP6500_1-PadSTEP)") (class "Default")
      (node (ref "MP6500_1") (pin "STEP") (pinfunction "STEP_STEP") (pintype "bidirectional"))
      (node (ref "TEENSY4.1") (pin "10/CS") (pinfunction "10/CS_10/CS") (pintype "bidirectional"))
    )
    (net (code "63") (name "Net-(MP6500_2-PadDIR)") (class "Default")
      (node (ref "MP6500_2") (pin "DIR") (pinfunction "DIR_DIR") (pintype "bidirectional"))
      (node (ref "TEENSY4.1") (pin "29") (pinfunction "29_29") (pintype "bidirectional"))
    )
    (net (code "64") (name "Net-(MP6500_2-PadI1)") (class "Default")
      (node (ref "MP6500_2") (pin "I1") (pinfunction "I1_I1") (pintype "bidirectional"))
      (node (ref "TEENSY4.1") (pin "24") (pinfunction "24_24") (pintype "bidirectional"))
    )
    (net (code "65") (name "Net-(MP6500_2-PadI2)") (class "Default")
      (node (ref "MP6500_2") (pin "I2") (pinfunction "I2_I2") (pintype "bidirectional"))
      (node (ref "TEENSY4.1") (pin "25") (pinfunction "25_25") (pintype "bidirectional"))
    )
    (net (code "66") (name "Net-(MP6500_2-PadSTEP)") (class "Default")
      (node (ref "MP6500_2") (pin "STEP") (pinfunction "STEP_STEP") (pintype "bidirectional"))
      (node (ref "TEENSY4.1") (pin "28") (pinfunction "28_28") (pintype "bidirectional"))
    )
    (net (code "67") (name "Net-(POT1_A-PadMP)") (class "Default")
      (node (ref "POT1_A") (pin "MP") (pinfunction "MP_MP") (pintype "passive"))
      (node (ref "TEENSY4.1") (pin "22/A8") (pinfunction "22/A8_22/A8") (pintype "bidirectional"))
    )
    (net (code "68") (name "Net-(POT2_A-PadMP)") (class "Default")
      (node (ref "POT2_A") (pin "MP") (pinfunction "MP_MP") (pintype "passive"))
      (node (ref "TEENSY4.1") (pin "21/A7") (pinfunction "21/A7_21/A7") (pintype "bidirectional"))
    )
    (net (code "69") (name "Net-(POT3_A-PadMP)") (class "Default")
      (node (ref "POT3_A") (pin "MP") (pinfunction "MP_MP") (pintype "passive"))
      (node (ref "TEENSY4.1") (pin "20/A6") (pinfunction "20/A6_20/A6") (pintype "bidirectional"))
    )
    (net (code "70") (name "Net-(POT4_A-PadMP)") (class "Default")
      (node (ref "POT4_A") (pin "MP") (pinfunction "MP_MP") (pintype "passive"))
      (node (ref "TEENSY4.1") (pin "19/A5/SCL") (pinfunction "19/A5/SCL_19/A5/SCL") (pintype "bidirectional"))
    )
    (net (code "71") (name "Net-(POT5_A-PadMP)") (class "Default")
      (node (ref "POT5_A") (pin "MP") (pinfunction "MP_MP") (pintype "passive"))
      (node (ref "TEENSY4.1") (pin "18/A4/SDA") (pinfunction "18/A4/SDA_18/A4/SDA") (pintype "bidirectional"))
    )
    (net (code "72") (name "Net-(POT6_A-PadMP)") (class "Default")
      (node (ref "POT6_A") (pin "MP") (pinfunction "MP_MP") (pintype "passive"))
      (node (ref "TEENSY4.1") (pin "23/A9") (pinfunction "23/A9_23/A9") (pintype "bidirectional"))
    )
    (net (code "73") (name "Net-(TEENSY4.1-A21{slash}DAC0)") (class "Default")
      (node (ref "LS4_A3") (pin "MP") (pinfunction "MP_MP") (pintype "passive"))
      (node (ref "TEENSY4.1") (pin "21/DAC0") (pinfunction "A21/DAC0_21/DAC0") (pintype "bidirectional"))
    )
    (net (code "74") (name "unconnected-(MP6500_1-EN-PadENBL)") (class "Default")
      (node (ref "MP6500_1") (pin "ENBL") (pinfunction "EN_ENBL") (pintype "bidirectional"))
    )
    (net (code "75") (name "unconnected-(MP6500_1-FLT-PadFAULT)") (class "Default")
      (node (ref "MP6500_1") (pin "FAULT") (pinfunction "FLT_FAULT") (pintype "bidirectional"))
    )
    (net (code "76") (name "unconnected-(MP6500_1-PadMS1)") (class "Default")
      (node (ref "MP6500_1") (pin "MS1") (pinfunction "MS1_MS1") (pintype "bidirectional"))
    )
    (net (code "77") (name "unconnected-(MP6500_1-PadMS2)") (class "Default")
      (node (ref "MP6500_1") (pin "MS2") (pinfunction "MS2_MS2") (pintype "bidirectional"))
    )
    (net (code "78") (name "unconnected-(MP6500_2-EN-PadENBL)") (class "Default")
      (node (ref "MP6500_2") (pin "ENBL") (pinfunction "EN_ENBL") (pintype "bidirectional"))
    )
    (net (code "79") (name "unconnected-(MP6500_2-FLT-PadFAULT)") (class "Default")
      (node (ref "MP6500_2") (pin "FAULT") (pinfunction "FLT_FAULT") (pintype "bidirectional"))
    )
    (net (code "80") (name "unconnected-(MP6500_2-PadMS1)") (class "Default")
      (node (ref "MP6500_2") (pin "MS1") (pinfunction "MS1_MS1") (pintype "bidirectional"))
    )
    (net (code "81") (name "unconnected-(MP6500_2-PadMS2)") (class "Default")
      (node (ref "MP6500_2") (pin "MS2") (pinfunction "MS2_MS2") (pintype "bidirectional"))
    )
    (net (code "82") (name "unconnected-(TEENSY4.1-Pad3V3_2)") (class "Default")
      (node (ref "TEENSY4.1") (pin "3V3_2") (pinfunction "3V3_2_3V3_2") (pintype "bidirectional"))
    )
    (net (code "83") (name "unconnected-(TEENSY4.1-Pad12{slash}MISO)") (class "Default")
      (node (ref "TEENSY4.1") (pin "12/MISO") (pinfunction "12/MISO_12/MISO") (pintype "bidirectional"))
    )
    (net (code "84") (name "unconnected-(TEENSY4.1-Pad26)") (class "Default")
      (node (ref "TEENSY4.1") (pin "26") (pinfunction "26_26") (pintype "bidirectional"))
    )
    (net (code "85") (name "unconnected-(TEENSY4.1-Pad27)") (class "Default")
      (node (ref "TEENSY4.1") (pin "27") (pinfunction "27_27") (pintype "bidirectional"))
    )
    (net (code "86") (name "unconnected-(TEENSY4.1-Pad30)") (class "Default")
      (node (ref "TEENSY4.1") (pin "30") (pinfunction "30_30") (pintype "bidirectional"))
    )
    (net (code "87") (name "unconnected-(TEENSY4.1-Pad31{slash}A12)") (class "Default")
      (node (ref "TEENSY4.1") (pin "31/A12") (pinfunction "31/A12_31/A12") (pintype "bidirectional"))
    )
    (net (code "88") (name "unconnected-(TEENSY4.1-Pad32{slash}A13)") (class "Default")
      (node (ref "TEENSY4.1") (pin "32/A13") (pinfunction "32/A13_32/A13") (pintype "bidirectional"))
    )
    (net (code "89") (name "unconnected-(TEENSY4.1-Pad33{slash}A14)") (class "Default")
      (node (ref "TEENSY4.1") (pin "33/A14") (pinfunction "33/A14_33/A14") (pintype "bidirectional"))
    )
    (net (code "90") (name "unconnected-(TEENSY4.1-Pad34{slash}A15)") (class "Default")
      (node (ref "TEENSY4.1") (pin "34/A15") (pinfunction "34/A15_34/A15") (pintype "bidirectional"))
    )
    (net (code "91") (name "unconnected-(TEENSY4.1-PadA10)") (class "Default")
      (node (ref "TEENSY4.1") (pin "A10") (pinfunction "A10_A10") (pintype "bidirectional"))
    )
    (net (code "92") (name "unconnected-(TEENSY4.1-PadA11)") (class "Default")
      (node (ref "TEENSY4.1") (pin "A11") (pinfunction "A11_A11") (pintype "bidirectional"))
    )
    (net (code "93") (name "unconnected-(TEENSY4.1-PadAGND)") (class "Default")
      (node (ref "TEENSY4.1") (pin "AGND") (pinfunction "AGND_AGND") (pintype "bidirectional"))
    )
    (net (code "94") (name "unconnected-(TEENSY4.1-PadAREF)") (class "Default")
      (node (ref "TEENSY4.1") (pin "AREF") (pinfunction "AREF_AREF") (pintype "bidirectional"))
    )
    (net (code "95") (name "unconnected-(TEENSY4.1-PadGND2)") (class "Default")
      (node (ref "TEENSY4.1") (pin "GND2") (pinfunction "GND2_GND2") (pintype "bidirectional"))
    )
    (net (code "96") (name "unconnected-(TEENSY4.1-PadGND3)") (class "Default")
      (node (ref "TEENSY4.1") (pin "GND3") (pinfunction "GND3_GND3") (pintype "bidirectional"))
    )
    (net (code "97") (name "unconnected-(TEENSY4.1-PadPROG)") (class "Default")
      (node (ref "TEENSY4.1") (pin "PROG") (pinfunction "PROG_PROG") (pintype "bidirectional"))
    )
    (net (code "98") (name "unconnected-(TEENSY4.1-PadRESET)") (class "Default")
      (node (ref "TEENSY4.1") (pin "RESET") (pinfunction "RESET_RESET") (pintype "bidirectional"))
    )
    (net (code "99") (name "unconnected-(TEENSY4.1-PadU5V)") (class "Default")
      (node (ref "TEENSY4.1") (pin "U5V") (pinfunction "U5V_U5V") (pintype "bidirectional"))
    )
    (net (code "100") (name "unconnected-(TEENSY4.1-PadUD+)") (class "Default")
      (node (ref "TEENSY4.1") (pin "UD+") (pinfunction "UD+_UD+") (pintype "bidirectional"))
    )
    (net (code "101") (name "unconnected-(TEENSY4.1-PadUD-)") (class "Default")
      (node (ref "TEENSY4.1") (pin "UD-") (pinfunction "UD-_UD-") (pintype "bidirectional"))
    )
    (net (code "102") (name "unconnected-(TEENSY4.1-PadUGND1)") (class "Default")
      (node (ref "TEENSY4.1") (pin "UGND1") (pinfunction "UGND1_UGND1") (pintype "bidirectional"))
    )
    (net (code "103") (name "unconnected-(TEENSY4.1-PadUGND2)") (class "Default")
      (node (ref "TEENSY4.1") (pin "UGND2") (pinfunction "UGND2_UGND2") (pintype "bidirectional"))
    )
    (net (code "104") (name "unconnected-(TEENSY4.1-PadVBAT)") (class "Default")
      (node (ref "TEENSY4.1") (pin "VBAT") (pinfunction "VBAT_VBAT") (pintype "bidirectional"))
    )
    (net (code "105") (name "unconnected-(TEENSY4.1-PadVUSB)") (class "Default")
      (node (ref "TEENSY4.1") (pin "VUSB") (pinfunction "VUSB_VUSB") (pintype "bidirectional"))
    )
  )
)
